# espscrew12e.net
KiCad netlist of a schematic drawn in EAGLE
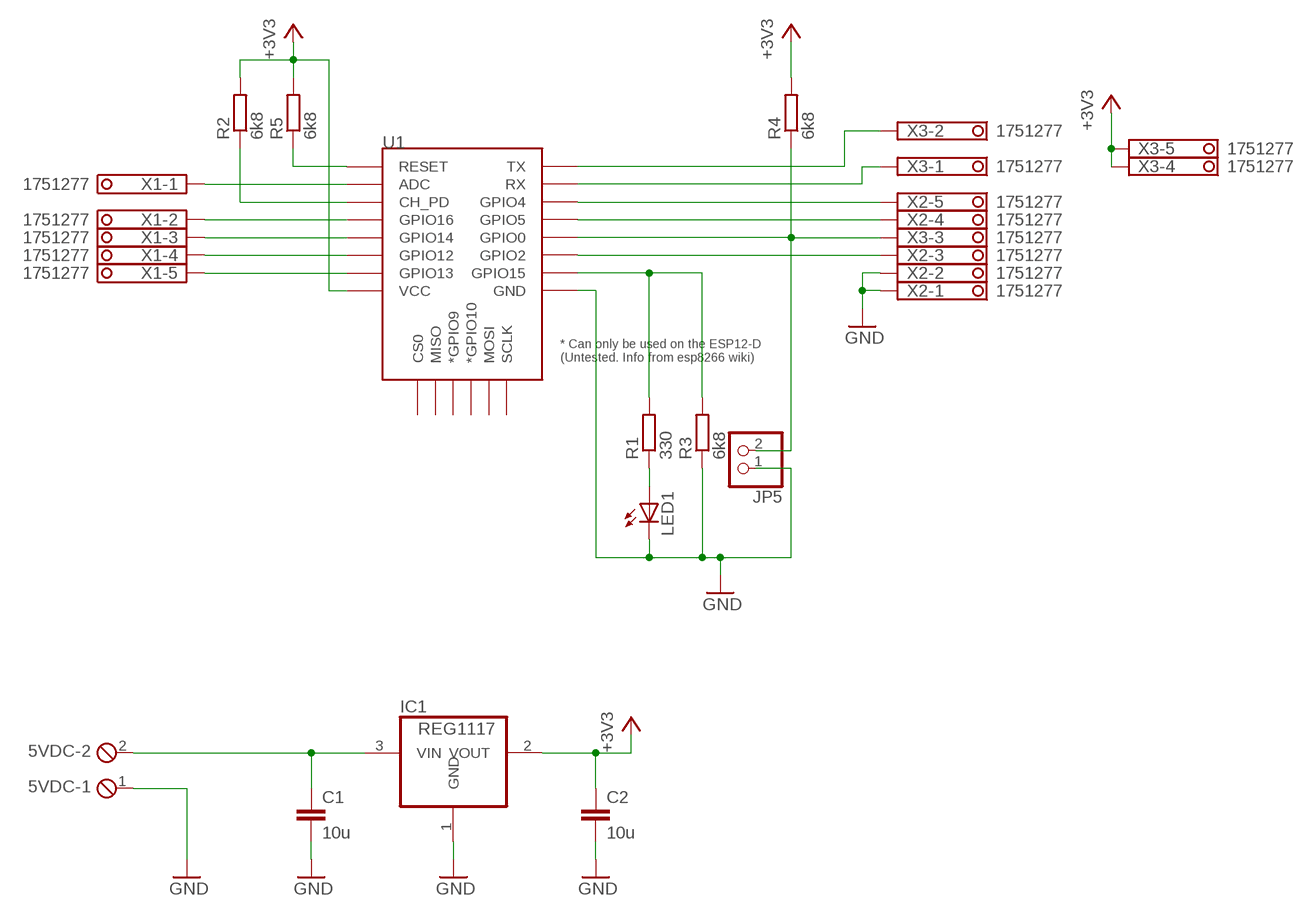
[diagram p0: schematic, sheet 1]

(export (version "E")
  (design (tool "Eeschema 10.0.6"))
  (components
    (comp (ref "5VDC")
      (value "MPT2")
      (footprint "eagle-import:2POL254")
      (libsource (lib "eagle-import") (part "MPT2"))
    )
    (comp (ref "C1")
      (value "10u")
      (footprint "eagle-import:C1206K")
      (libsource (lib "eagle-import") (part "C-EUC1206K"))
    )
    (comp (ref "C2")
      (value "10u")
      (footprint "eagle-import:C1206K")
      (libsource (lib "eagle-import") (part "C-EUC1206K"))
    )
    (comp (ref "IC1")
      (value "REG1117")
      (footprint "eagle-import:SOT223")
      (libsource (lib "eagle-import") (part "REG1117"))
    )
    (comp (ref "JP5")
      (value "PINHD-1X2")
      (footprint "eagle-import:1X02")
      (libsource (lib "eagle-import") (part "PINHD-1X2"))
    )
    (comp (ref "LED1")
      (value "LEDSML1206")
      (footprint "eagle-import:SML1206")
      (libsource (lib "eagle-import") (part "LEDSML1206"))
    )
    (comp (ref "R1")
      (value "330")
      (footprint "eagle-import:R1206")
      (libsource (lib "eagle-import") (part "R-EU_R1206"))
    )
    (comp (ref "R2")
      (value "6k8")
      (footprint "eagle-import:R1206")
      (libsource (lib "eagle-import") (part "R-EU_R1206"))
    )
    (comp (ref "R3")
      (value "6k8")
      (footprint "eagle-import:R1206")
      (libsource (lib "eagle-import") (part "R-EU_R1206"))
    )
    (comp (ref "R4")
      (value "6k8")
      (footprint "eagle-import:R1206")
      (libsource (lib "eagle-import") (part "R-EU_R1206"))
    )
    (comp (ref "R5")
      (value "6k8")
      (footprint "eagle-import:R1206")
      (libsource (lib "eagle-import") (part "R-EU_R1206"))
    )
    (comp (ref "U1")
      (value "ESP12ESMD")
      (footprint "eagle-import:ESP12E-SMD")
      (libsource (lib "eagle-import") (part "ESP12ESMD"))
    )
    (comp (ref "X1")
      (value "1751277")
      (footprint "eagle-import:1751277")
      (libsource (lib "eagle-import") (part "1751277"))
    )
    (comp (ref "X2")
      (value "1751277")
      (footprint "eagle-import:1751277")
      (libsource (lib "eagle-import") (part "1751277"))
    )
    (comp (ref "X3")
      (value "1751277")
      (footprint "eagle-import:1751277")
      (libsource (lib "eagle-import") (part "1751277"))
    )
  )
  (nets
    (net (code "1") (name "+3V3") (class "Default")
      (node (ref "C2") (pin "1") (pinfunction "1_1") (pintype "passive"))
      (node (ref "IC1") (pin "2") (pinfunction "VOUT_2") (pintype "output"))
      (node (ref "R2") (pin "2") (pinfunction "2_2") (pintype "passive"))
      (node (ref "R4") (pin "2") (pinfunction "2_2") (pintype "passive"))
      (node (ref "R5") (pin "2") (pinfunction "2_2") (pintype "passive"))
      (node (ref "U1") (pin "VCC") (pinfunction "VCC_VCC") (pintype "bidirectional"))
      (node (ref "X3") (pin "4") (pinfunction "K_4") (pintype "passive"))
      (node (ref "X3") (pin "5") (pinfunction "K_5") (pintype "passive"))
    )
    (net (code "2") (name "GND") (class "Default")
      (node (ref "5VDC") (pin "1") (pinfunction "1_1") (pintype "passive"))
      (node (ref "C1") (pin "2") (pinfunction "2_2") (pintype "passive"))
      (node (ref "C2") (pin "2") (pinfunction "2_2") (pintype "passive"))
      (node (ref "IC1") (pin "1") (pinfunction "GND_1") (pintype "power_in"))
      (node (ref "JP5") (pin "1") (pinfunction "1_1") (pintype "passive"))
      (node (ref "LED1") (pin "C") (pinfunction "C_C") (pintype "passive"))
      (node (ref "R3") (pin "1") (pinfunction "1_1") (pintype "passive"))
      (node (ref "U1") (pin "GND") (pinfunction "GND_GND") (pintype "bidirectional"))
      (node (ref "X2") (pin "1") (pinfunction "K_1") (pintype "passive"))
      (node (ref "X2") (pin "2") (pinfunction "K_2") (pintype "passive"))
    )
    (net (code "3") (name "Net-(5VDCB-1)") (class "Default")
      (node (ref "5VDC") (pin "2") (pinfunction "1_2") (pintype "passive"))
      (node (ref "C1") (pin "1") (pinfunction "1_1") (pintype "passive"))
      (node (ref "IC1") (pin "3") (pinfunction "VIN_3") (pintype "input"))
    )
    (net (code "4") (name "Net-(LED1-PadA)") (class "Default")
      (node (ref "LED1") (pin "A") (pinfunction "A_A") (pintype "passive"))
      (node (ref "R1") (pin "1") (pinfunction "1_1") (pintype "passive"))
    )
    (net (code "5") (name "Net-(R1-Pad2)") (class "Default")
      (node (ref "R1") (pin "2") (pinfunction "2_2") (pintype "passive"))
      (node (ref "R3") (pin "2") (pinfunction "2_2") (pintype "passive"))
      (node (ref "U1") (pin "GPIO15") (pinfunction "GPIO15_GPIO15") (pintype "bidirectional"))
    )
    (net (code "6") (name "Net-(R2-Pad1)") (class "Default")
      (node (ref "R2") (pin "1") (pinfunction "1_1") (pintype "passive"))
      (node (ref "U1") (pin "CH_PD") (pinfunction "CH_PD_CH_PD") (pintype "bidirectional"))
    )
    (net (code "7") (name "Net-(R5-Pad1)") (class "Default")
      (node (ref "R5") (pin "1") (pinfunction "1_1") (pintype "passive"))
      (node (ref "U1") (pin "RESET") (pinfunction "RESET_RESET") (pintype "bidirectional"))
    )
    (net (code "8") (name "Net-(U1-RX)") (class "Default")
      (node (ref "U1") (pin "RXD0") (pinfunction "RX_RXD0") (pintype "bidirectional"))
      (node (ref "X3") (pin "1") (pinfunction "K_1") (pintype "passive"))
    )
    (net (code "9") (name "Net-(U1-TX)") (class "Default")
      (node (ref "U1") (pin "TXD0") (pinfunction "TX_TXD0") (pintype "bidirectional"))
      (node (ref "X3") (pin "2") (pinfunction "K_2") (pintype "passive"))
    )
    (net (code "10") (name "Net-(X1A-K)") (class "Default")
      (node (ref "U1") (pin "ADC") (pinfunction "ADC_ADC") (pintype "bidirectional"))
      (node (ref "X1") (pin "1") (pinfunction "K_1") (pintype "passive"))
    )
    (net (code "11") (name "Net-(X1B-K)") (class "Default")
      (node (ref "U1") (pin "GPIO16") (pinfunction "GPIO16_GPIO16") (pintype "bidirectional"))
      (node (ref "X1") (pin "2") (pinfunction "K_2") (pintype "passive"))
    )
    (net (code "12") (name "Net-(X1C-K)") (class "Default")
      (node (ref "U1") (pin "GPIO14") (pinfunction "GPIO14_GPIO14") (pintype "bidirectional"))
      (node (ref "X1") (pin "3") (pinfunction "K_3") (pintype "passive"))
    )
    (net (code "13") (name "Net-(X1D-K)") (class "Default")
      (node (ref "U1") (pin "GPIO12") (pinfunction "GPIO12_GPIO12") (pintype "bidirectional"))
      (node (ref "X1") (pin "4") (pinfunction "K_4") (pintype "passive"))
    )
    (net (code "14") (name "Net-(X1E-K)") (class "Default")
      (node (ref "U1") (pin "GPIO13") (pinfunction "GPIO13_GPIO13") (pintype "bidirectional"))
      (node (ref "X1") (pin "5") (pinfunction "K_5") (pintype "passive"))
    )
    (net (code "15") (name "Net-(X2C-K)") (class "Default")
      (node (ref "U1") (pin "GPIO2") (pinfunction "GPIO2_GPIO2") (pintype "bidirectional"))
      (node (ref "X2") (pin "3") (pinfunction "K_3") (pintype "passive"))
    )
    (net (code "16") (name "Net-(X2D-K)") (class "Default")
      (node (ref "U1") (pin "GPIO5") (pinfunction "GPIO5_GPIO5") (pintype "bidirectional"))
      (node (ref "X2") (pin "4") (pinfunction "K_4") (pintype "passive"))
    )
    (net (code "17") (name "Net-(X2E-K)") (class "Default")
      (node (ref "U1") (pin "GPIO4") (pinfunction "GPIO4_GPIO4") (pintype "bidirectional"))
      (node (ref "X2") (pin "5") (pinfunction "K_5") (pintype "passive"))
    )
    (net (code "18") (name "Net-(X3C-K)") (class "Default")
      (node (ref "JP5") (pin "2") (pinfunction "2_2") (pintype "passive"))
      (node (ref "R4") (pin "1") (pinfunction "1_1") (pintype "passive"))
      (node (ref "U1") (pin "GPIO0") (pinfunction "GPIO0_GPIO0") (pintype "bidirectional"))
      (node (ref "X3") (pin "3") (pinfunction "K_3") (pintype "passive"))
    )
    (net (code "19") (name "unconnected-(U1-*GPIO9-PadGPIO9)") (class "Default")
      (node (ref "U1") (pin "GPIO9") (pinfunction "*GPIO9_GPIO9") (pintype "bidirectional"))
    )
    (net (code "20") (name "unconnected-(U1-*GPIO10-PadGPIO10)") (class "Default")
      (node (ref "U1") (pin "GPIO10") (pinfunction "*GPIO10_GPIO10") (pintype "bidirectional"))
    )
    (net (code "21") (name "unconnected-(U1-PadCS0)") (class "Default")
      (node (ref "U1") (pin "CS0") (pinfunction "CS0_CS0") (pintype "bidirectional"))
    )
    (net (code "22") (name "unconnected-(U1-PadMISO)") (class "Default")
      (node (ref "U1") (pin "MISO") (pinfunction "MISO_MISO") (pintype "bidirectional"))
    )
    (net (code "23") (name "unconnected-(U1-PadMOSI)") (class "Default")
      (node (ref "U1") (pin "MOSI") (pinfunction "MOSI_MOSI") (pintype "bidirectional"))
    )
    (net (code "24") (name "unconnected-(U1-PadSCLK)") (class "Default")
      (node (ref "U1") (pin "SCLK") (pinfunction "SCLK_SCLK") (pintype "bidirectional"))
    )
  )
)
